# usb2rs232esp.net
KiCad netlist of a schematic drawn in EAGLE
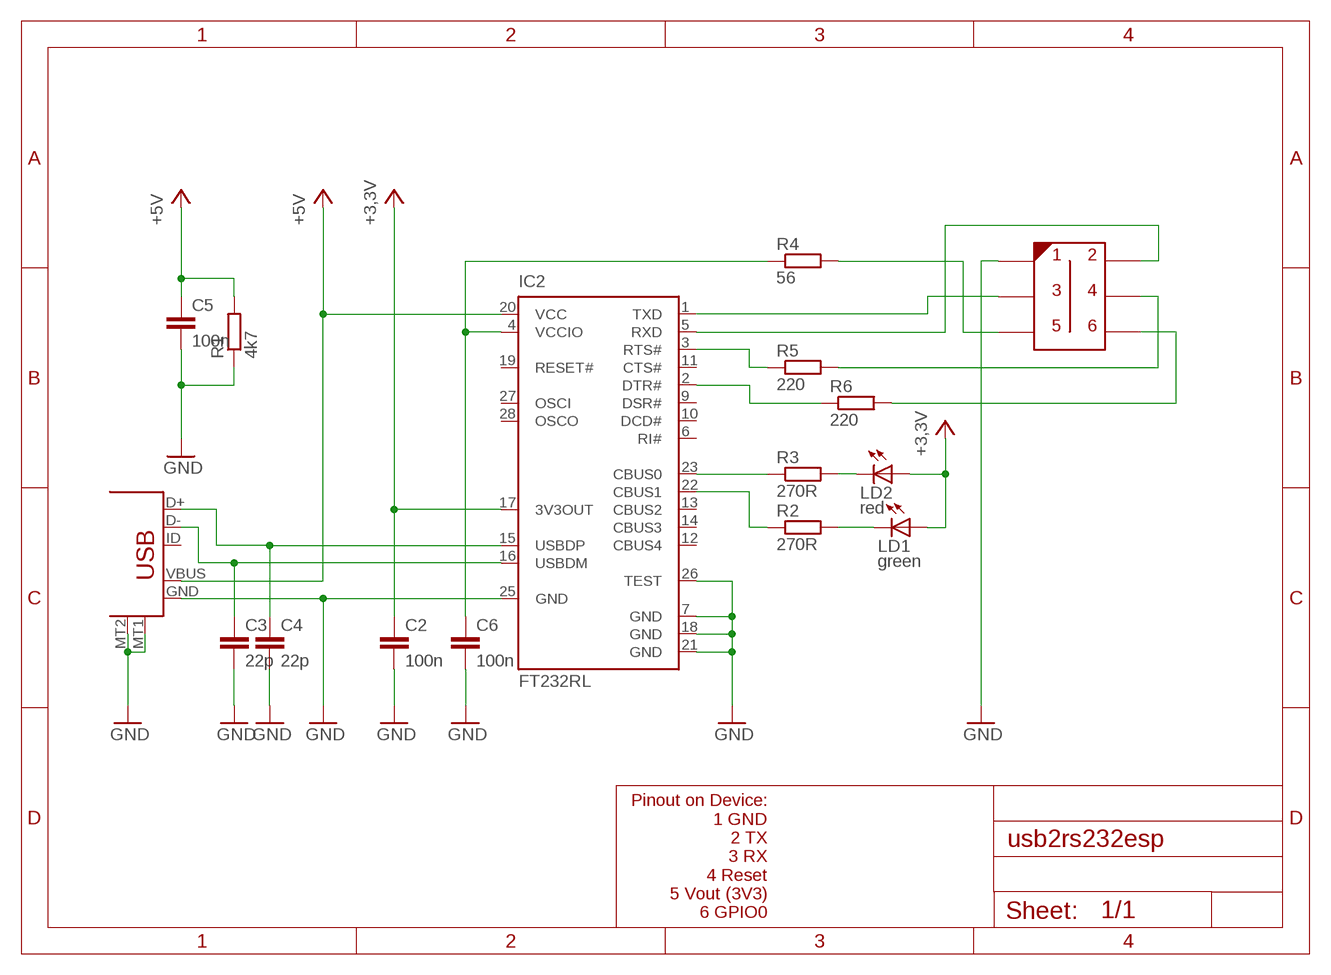
[diagram p0: schematic, sheet 1]

(export (version "E")
  (design (tool "Eeschema 10.0.6"))
  (components
    (comp (ref "C2")
      (value "100n")
      (footprint "eagle-import:C0603")
      (libsource (lib "eagle-import") (part "C-EUC0603"))
    )
    (comp (ref "C3")
      (value "22p")
      (footprint "eagle-import:C0603")
      (libsource (lib "eagle-import") (part "C-EUC0603"))
    )
    (comp (ref "C4")
      (value "22p")
      (footprint "eagle-import:C0603")
      (libsource (lib "eagle-import") (part "C-EUC0603"))
    )
    (comp (ref "C5")
      (value "100n")
      (footprint "eagle-import:C0603")
      (libsource (lib "eagle-import") (part "C-EUC0603"))
    )
    (comp (ref "C6")
      (value "100n")
      (footprint "eagle-import:C0603")
      (libsource (lib "eagle-import") (part "C-EUC0603"))
    )
    (comp (ref "IC2")
      (value "FT232RL")
      (footprint "eagle-import:SSOP28")
      (libsource (lib "eagle-import") (part "FT232RL"))
    )
    (comp (ref "LD1")
      (value "green")
      (footprint "eagle-import:CHIP-LED0603")
      (libsource (lib "eagle-import") (part "LEDCHIP-LED0603"))
    )
    (comp (ref "LD2")
      (value "red")
      (footprint "eagle-import:CHIP-LED0603")
      (libsource (lib "eagle-import") (part "LEDCHIP-LED0603"))
    )
    (comp (ref "R1")
      (value "4k7")
      (footprint "eagle-import:R0603")
      (libsource (lib "eagle-import") (part "R-EU_R0603"))
    )
    (comp (ref "R2")
      (value "270R")
      (footprint "eagle-import:R0603")
      (libsource (lib "eagle-import") (part "R-EU_R0603"))
    )
    (comp (ref "R3")
      (value "270R")
      (footprint "eagle-import:R0603")
      (libsource (lib "eagle-import") (part "R-EU_R0603"))
    )
    (comp (ref "R4")
      (value "56")
      (footprint "eagle-import:R0603")
      (libsource (lib "eagle-import") (part "R-EU_R0603"))
    )
    (comp (ref "R5")
      (value "220")
      (footprint "eagle-import:R0603")
      (libsource (lib "eagle-import") (part "R-EU_R0603"))
    )
    (comp (ref "R6")
      (value "220")
      (footprint "eagle-import:R0603")
      (libsource (lib "eagle-import") (part "R-EU_R0603"))
    )
    (comp (ref "U$3")
      (value "AVR-ISP-6-EDGE")
      (footprint "eagle-import:6PAD_ISP")
      (libsource (lib "eagle-import") (part "AVR-ISP-6-EDGE"))
    )
    (comp (ref "U$40")
      (value "USB-B")
      (footprint "eagle-import:USB-MICROB")
      (libsource (lib "eagle-import") (part "USB-B"))
    )
  )
  (nets
    (net (code "1") (name "+3,3V") (class "Default")
      (node (ref "C2") (pin "1") (pinfunction "1_1") (pintype "passive"))
      (node (ref "IC2") (pin "17") (pinfunction "3V3OUT_17") (pintype "input"))
      (node (ref "LD1") (pin "A") (pinfunction "A_A") (pintype "passive"))
      (node (ref "LD2") (pin "A") (pinfunction "A_A") (pintype "passive"))
    )
    (net (code "2") (name "+5V") (class "Default")
      (node (ref "C5") (pin "1") (pinfunction "1_1") (pintype "passive"))
      (node (ref "IC2") (pin "20") (pinfunction "VCC_20") (pintype "input"))
      (node (ref "R1") (pin "2") (pinfunction "2_2") (pintype "passive"))
      (node (ref "U$40") (pin "VBUS") (pinfunction "VBUS_VBUS") (pintype "bidirectional"))
    )
    (net (code "3") (name "GND") (class "Default")
      (node (ref "C2") (pin "2") (pinfunction "2_2") (pintype "passive"))
      (node (ref "C3") (pin "2") (pinfunction "2_2") (pintype "passive"))
      (node (ref "C4") (pin "2") (pinfunction "2_2") (pintype "passive"))
      (node (ref "C5") (pin "2") (pinfunction "2_2") (pintype "passive"))
      (node (ref "C6") (pin "2") (pinfunction "2_2") (pintype "passive"))
      (node (ref "IC2") (pin "18") (pinfunction "GND_18") (pintype "input"))
      (node (ref "IC2") (pin "21") (pinfunction "GND_21") (pintype "input"))
      (node (ref "IC2") (pin "25") (pinfunction "GND_25") (pintype "input"))
      (node (ref "IC2") (pin "26") (pinfunction "TEST_26") (pintype "input"))
      (node (ref "IC2") (pin "7") (pinfunction "GND_7") (pintype "input"))
      (node (ref "R1") (pin "1") (pinfunction "1_1") (pintype "passive"))
      (node (ref "U$3") (pin "MISO") (pinfunction "P$1_MISO") (pintype "bidirectional"))
      (node (ref "U$40") (pin "GND") (pinfunction "GND_GND") (pintype "bidirectional"))
      (node (ref "U$40") (pin "MT1") (pinfunction "P$1_MT1") (pintype "bidirectional"))
      (node (ref "U$40") (pin "MT2") (pinfunction "P$2_MT2") (pintype "bidirectional"))
    )
    (net (code "4") (name "Net-(IC2-CBUS0)") (class "Default")
      (node (ref "IC2") (pin "23") (pinfunction "CBUS0_23") (pintype "input"))
      (node (ref "R3") (pin "1") (pinfunction "1_1") (pintype "passive"))
    )
    (net (code "5") (name "Net-(IC2-CBUS1)") (class "Default")
      (node (ref "IC2") (pin "22") (pinfunction "CBUS1_22") (pintype "input"))
      (node (ref "R2") (pin "1") (pinfunction "1_1") (pintype "passive"))
    )
    (net (code "6") (name "Net-(IC2-DTR#)") (class "Default")
      (node (ref "IC2") (pin "2") (pinfunction "DTR#_2") (pintype "input"))
      (node (ref "R6") (pin "1") (pinfunction "1_1") (pintype "passive"))
    )
    (net (code "7") (name "Net-(IC2-RTS#)") (class "Default")
      (node (ref "IC2") (pin "3") (pinfunction "RTS#_3") (pintype "input"))
      (node (ref "R5") (pin "1") (pinfunction "1_1") (pintype "passive"))
    )
    (net (code "8") (name "Net-(IC2-RXD)") (class "Default")
      (node (ref "IC2") (pin "5") (pinfunction "RXD_5") (pintype "input"))
      (node (ref "U$3") (pin "VCC") (pinfunction "P$6_VCC") (pintype "bidirectional"))
    )
    (net (code "9") (name "Net-(IC2-TXD)") (class "Default")
      (node (ref "IC2") (pin "1") (pinfunction "TXD_1") (pintype "input"))
      (node (ref "U$3") (pin "SCK") (pinfunction "P$2_SCK") (pintype "bidirectional"))
    )
    (net (code "10") (name "Net-(IC2-USBDM)") (class "Default")
      (node (ref "C3") (pin "1") (pinfunction "1_1") (pintype "passive"))
      (node (ref "IC2") (pin "16") (pinfunction "USBDM_16") (pintype "input"))
      (node (ref "U$40") (pin "D-") (pinfunction "D-_D-") (pintype "bidirectional"))
    )
    (net (code "11") (name "Net-(IC2-USBDP)") (class "Default")
      (node (ref "C4") (pin "1") (pinfunction "1_1") (pintype "passive"))
      (node (ref "IC2") (pin "15") (pinfunction "USBDP_15") (pintype "input"))
      (node (ref "U$40") (pin "D+") (pinfunction "D+_D+") (pintype "bidirectional"))
    )
    (net (code "12") (name "Net-(IC2-VCCIO)") (class "Default")
      (node (ref "C6") (pin "1") (pinfunction "1_1") (pintype "passive"))
      (node (ref "IC2") (pin "4") (pinfunction "VCCIO_4") (pintype "input"))
      (node (ref "R4") (pin "1") (pinfunction "1_1") (pintype "passive"))
    )
    (net (code "13") (name "Net-(LD1-PadC)") (class "Default")
      (node (ref "LD1") (pin "C") (pinfunction "C_C") (pintype "passive"))
      (node (ref "R2") (pin "2") (pinfunction "2_2") (pintype "passive"))
    )
    (net (code "14") (name "Net-(LD2-PadC)") (class "Default")
      (node (ref "LD2") (pin "C") (pinfunction "C_C") (pintype "passive"))
      (node (ref "R3") (pin "2") (pinfunction "2_2") (pintype "passive"))
    )
    (net (code "15") (name "Net-(U$3-P$3)") (class "Default")
      (node (ref "R4") (pin "2") (pinfunction "2_2") (pintype "passive"))
      (node (ref "U$3") (pin "RST") (pinfunction "P$3_RST") (pintype "bidirectional"))
    )
    (net (code "16") (name "Net-(U$3-P$4)") (class "Default")
      (node (ref "R6") (pin "2") (pinfunction "2_2") (pintype "passive"))
      (node (ref "U$3") (pin "GND") (pinfunction "P$4_GND") (pintype "bidirectional"))
    )
    (net (code "17") (name "Net-(U$3-P$5)") (class "Default")
      (node (ref "R5") (pin "2") (pinfunction "2_2") (pintype "passive"))
      (node (ref "U$3") (pin "MOSI") (pinfunction "P$5_MOSI") (pintype "bidirectional"))
    )
    (net (code "18") (name "unconnected-(IC2-CBUS2-Pad13)") (class "Default")
      (node (ref "IC2") (pin "13") (pinfunction "CBUS2_13") (pintype "input"))
    )
    (net (code "19") (name "unconnected-(IC2-CBUS3-Pad14)") (class "Default")
      (node (ref "IC2") (pin "14") (pinfunction "CBUS3_14") (pintype "input"))
    )
    (net (code "20") (name "unconnected-(IC2-CBUS4-Pad12)") (class "Default")
      (node (ref "IC2") (pin "12") (pinfunction "CBUS4_12") (pintype "input"))
    )
    (net (code "21") (name "unconnected-(IC2-CTS#-Pad11)") (class "Default")
      (node (ref "IC2") (pin "11") (pinfunction "CTS#_11") (pintype "input"))
    )
    (net (code "22") (name "unconnected-(IC2-DCD#-Pad10)") (class "Default")
      (node (ref "IC2") (pin "10") (pinfunction "DCD#_10") (pintype "input"))
    )
    (net (code "23") (name "unconnected-(IC2-DSR#-Pad9)") (class "Default")
      (node (ref "IC2") (pin "9") (pinfunction "DSR#_9") (pintype "input"))
    )
    (net (code "24") (name "unconnected-(IC2-OSCI-Pad27)") (class "Default")
      (node (ref "IC2") (pin "27") (pinfunction "OSCI_27") (pintype "input"))
    )
    (net (code "25") (name "unconnected-(IC2-OSCO-Pad28)") (class "Default")
      (node (ref "IC2") (pin "28") (pinfunction "OSCO_28") (pintype "input"))
    )
    (net (code "26") (name "unconnected-(IC2-RESET#-Pad19)") (class "Default")
      (node (ref "IC2") (pin "19") (pinfunction "RESET#_19") (pintype "input"))
    )
    (net (code "27") (name "unconnected-(IC2-RI#-Pad6)") (class "Default")
      (node (ref "IC2") (pin "6") (pinfunction "RI#_6") (pintype "input"))
    )
    (net (code "28") (name "unconnected-(U$40-PadID)") (class "Default")
      (node (ref "U$40") (pin "ID") (pinfunction "ID_ID") (pintype "bidirectional"))
    )
  )
)
